# tricorder-light-sensors-mk-2_0.net
KiCad netlist of a schematic drawn in EAGLE
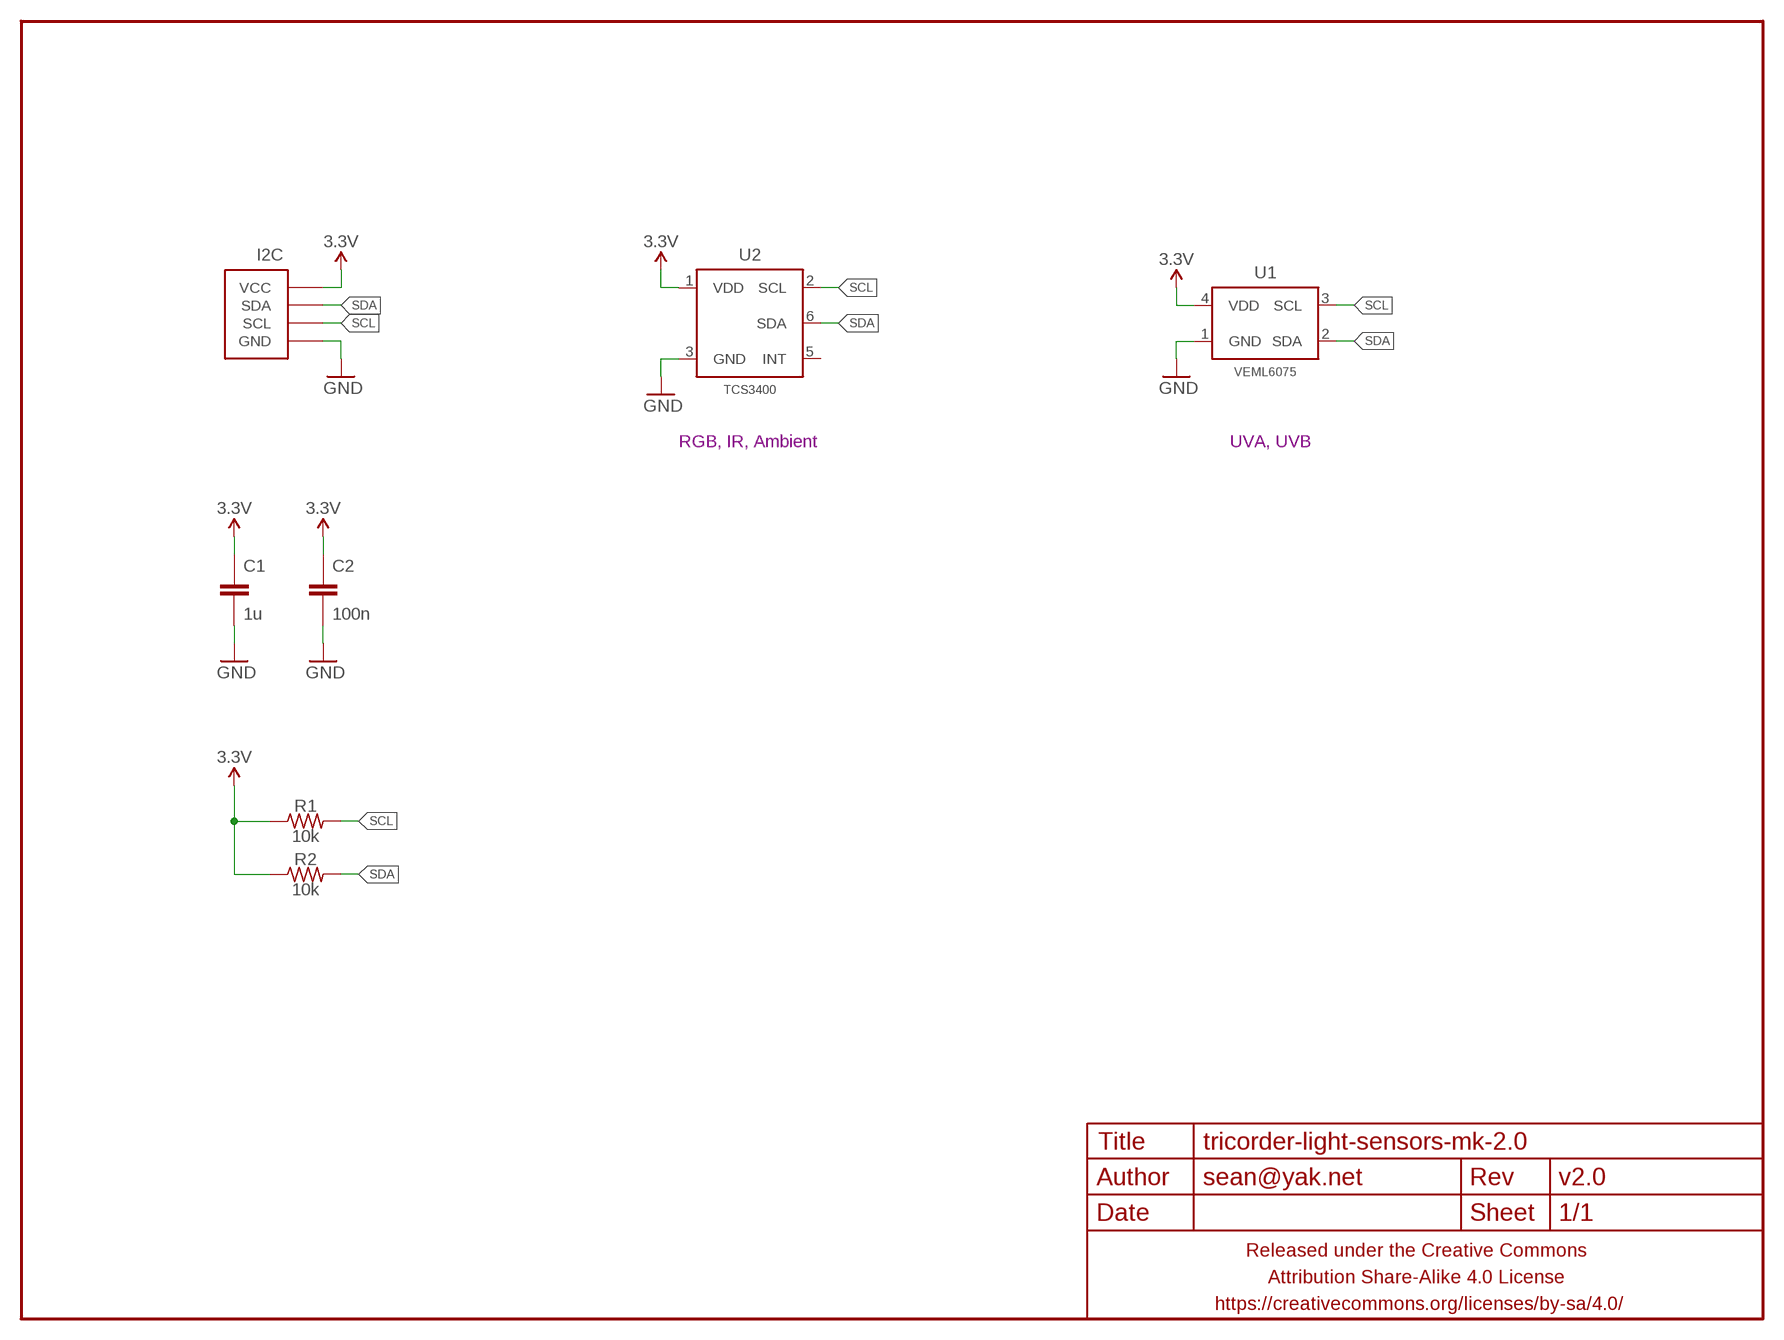
[diagram p0: schematic, sheet 1]

(export (version "E")
  (design (tool "Eeschema 10.0.6"))
  (components
    (comp (ref "C1")
      (value "1u")
      (footprint "eagle-import:C0603")
      (libsource (lib "eagle-import") (part "CAPACITOR-CERAMICC0603"))
    )
    (comp (ref "C2")
      (value "100n")
      (footprint "eagle-import:C0603")
      (libsource (lib "eagle-import") (part "CAPACITOR-CERAMICC0603"))
    )
    (comp (ref "FRAME1")
      (value "FRAME-LETTERNO_PACKAGE")
      (footprint "eagle-import:DUMMY")
      (fields (field (name "DESIGNER") "sean@yak.net") (field (name "VERSION") "v2.0"))
      (libsource (lib "eagle-import") (part "FRAME-LETTERNO_PACKAGE"))
    )
    (comp (ref "I2C")
      (value "M04-I2CPTH-0.1IN-CENTERED")
      (footprint "eagle-import:1X04-PTH-VERT-I2C-CENTERED")
      (libsource (lib "eagle-import") (part "M04-I2CPTH-0.1IN-CENTERED"))
    )
    (comp (ref "R1")
      (value "10k")
      (footprint "eagle-import:R0603")
      (libsource (lib "eagle-import") (part "RESISTORR0603"))
    )
    (comp (ref "R2")
      (value "10k")
      (footprint "eagle-import:R0603")
      (libsource (lib "eagle-import") (part "RESISTORR0603"))
    )
    (comp (ref "U1")
      (value "VEML6075")
      (footprint "eagle-import:OPLGA4")
      (libsource (lib "eagle-import") (part "VEML6075"))
    )
    (comp (ref "U2")
      (value "TCS3400")
      (footprint "eagle-import:TCS3400_DFN6")
      (libsource (lib "eagle-import") (part "TCS3400DFN6"))
    )
  )
  (nets
    (net (code "1") (name "3.3V") (class "Default")
      (node (ref "C1") (pin "1") (pinfunction "1_1") (pintype "passive"))
      (node (ref "C2") (pin "1") (pinfunction "1_1") (pintype "passive"))
      (node (ref "I2C") (pin "VCC") (pinfunction "VCC_VCC") (pintype "bidirectional"))
      (node (ref "R1") (pin "1") (pinfunction "1_1") (pintype "passive"))
      (node (ref "R2") (pin "1") (pinfunction "1_1") (pintype "passive"))
      (node (ref "U1") (pin "4") (pinfunction "VDD_4") (pintype "bidirectional"))
      (node (ref "U2") (pin "1") (pinfunction "VDD_1") (pintype "bidirectional"))
    )
    (net (code "2") (name "GND") (class "Default")
      (node (ref "C1") (pin "2") (pinfunction "2_2") (pintype "passive"))
      (node (ref "C2") (pin "2") (pinfunction "2_2") (pintype "passive"))
      (node (ref "I2C") (pin "GND") (pinfunction "GND_GND") (pintype "bidirectional"))
      (node (ref "U1") (pin "1") (pinfunction "GND_1") (pintype "bidirectional"))
      (node (ref "U2") (pin "3") (pinfunction "GND_3") (pintype "bidirectional"))
    )
    (net (code "3") (name "SCL") (class "Default")
      (node (ref "I2C") (pin "SCL") (pinfunction "SCL_SCL") (pintype "bidirectional"))
      (node (ref "R1") (pin "2") (pinfunction "2_2") (pintype "passive"))
      (node (ref "U1") (pin "3") (pinfunction "SCL_3") (pintype "bidirectional"))
      (node (ref "U2") (pin "2") (pinfunction "SCL_2") (pintype "bidirectional"))
    )
    (net (code "4") (name "SDA") (class "Default")
      (node (ref "I2C") (pin "SDA") (pinfunction "SDA_SDA") (pintype "bidirectional"))
      (node (ref "R2") (pin "2") (pinfunction "2_2") (pintype "passive"))
      (node (ref "U1") (pin "2") (pinfunction "SDA_2") (pintype "bidirectional"))
      (node (ref "U2") (pin "6") (pinfunction "SDA_6") (pintype "bidirectional"))
    )
    (net (code "5") (name "unconnected-(U2-INT-Pad5)") (class "Default")
      (node (ref "U2") (pin "5") (pinfunction "INT_5") (pintype "bidirectional"))
    )
  )
)
